# Sheet1.net
KiCad netlist of a schematic drawn in Altium Designer
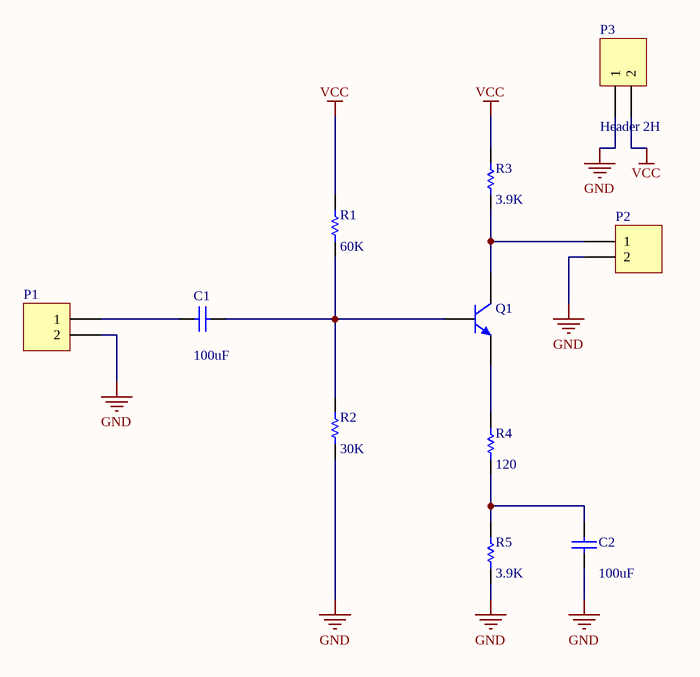
[diagram p0: Sheet1.SchDoc]

(export (version "E")
  (design (tool "Eeschema 10.0.6"))
  (components
    (comp (ref "C1")
      (value "100uF")
      (footprint "RAD-0.3")
      (description "Capacitor")
      (fields (field (name "Comment") "Cap") (field (name "PUBLISHER") "Altium Limited"))
      (libsource (lib "Miscellaneous Devices") (part "Cap"))
    )
    (comp (ref "C2")
      (value "100uF")
      (footprint "RAD-0.3")
      (description "Capacitor")
      (fields (field (name "Comment") "Cap") (field (name "PUBLISHER") "Altium Limited"))
      (libsource (lib "Miscellaneous Devices") (part "Cap"))
    )
    (comp (ref "P1")
      (value "Header 2H")
      (footprint "HDR1X2H")
      (description "Header, 2-Pin, Right Angle")
      (fields (field (name "PUBLISHER") "Altium Limited"))
      (libsource (lib "Miscellaneous Connectors") (part "Header 2H"))
    )
    (comp (ref "P2")
      (value "Header 2H")
      (footprint "HDR1X2H")
      (description "Header, 2-Pin, Right Angle")
      (fields (field (name "PUBLISHER") "Altium Limited"))
      (libsource (lib "") (part "Header 2H_1"))
    )
    (comp (ref "P3")
      (value "Header 2H")
      (footprint "HDR1X2H")
      (description "Header, 2-Pin, Right Angle")
      (fields (field (name "PUBLISHER") "Altium Limited"))
      (libsource (lib "") (part "Header 2H_2"))
    )
    (comp (ref "Q1")
      (value "BC548C")
      (footprint "29-04")
      (description "Amplifier Transistor NPN Silicon")
      (fields (field (name "PUBLISHER") "Altium Limited"))
      (libsource (lib "Motorola Discrete BJT") (part "BC548C"))
    )
    (comp (ref "R1")
      (value "60K")
      (footprint "AXIAL-0.3")
      (description "Resistor")
      (fields (field (name "Comment") "Res1") (field (name "PUBLISHER") "Altium Limited"))
      (libsource (lib "Miscellaneous Devices") (part "Res1"))
    )
    (comp (ref "R2")
      (value "30K")
      (footprint "AXIAL-0.3")
      (description "Resistor")
      (fields (field (name "Comment") "Res1") (field (name "PUBLISHER") "Altium Limited"))
      (libsource (lib "Miscellaneous Devices") (part "Res1"))
    )
    (comp (ref "R3")
      (value "3.9K")
      (footprint "AXIAL-0.3")
      (description "Resistor")
      (fields (field (name "Comment") "Res1") (field (name "PUBLISHER") "Altium Limited"))
      (libsource (lib "Miscellaneous Devices") (part "Res1"))
    )
    (comp (ref "R4")
      (value "120")
      (footprint "AXIAL-0.3")
      (description "Resistor")
      (fields (field (name "Comment") "Res1") (field (name "PUBLISHER") "Altium Limited"))
      (libsource (lib "Miscellaneous Devices") (part "Res1"))
    )
    (comp (ref "R5")
      (value "3.9K")
      (footprint "AXIAL-0.3")
      (description "Resistor")
      (fields (field (name "Comment") "Res1") (field (name "PUBLISHER") "Altium Limited"))
      (libsource (lib "Miscellaneous Devices") (part "Res1"))
    )
  )
  (nets
    (net (code "1") (name "GND") (class "Default")
      (node (ref "C2") (pin "1") (pinfunction "1_1") (pintype "passive"))
      (node (ref "P1") (pin "2") (pinfunction "2_2") (pintype "passive"))
      (node (ref "P2") (pin "2") (pinfunction "2_2") (pintype "passive"))
      (node (ref "P3") (pin "1") (pinfunction "1_1") (pintype "passive"))
      (node (ref "R2") (pin "1") (pinfunction "1_1") (pintype "passive"))
      (node (ref "R5") (pin "1") (pinfunction "1_1") (pintype "passive"))
    )
    (net (code "2") (name "Net-(C1-Pad1)") (class "Default")
      (node (ref "C1") (pin "1") (pinfunction "1_1") (pintype "passive"))
      (node (ref "P1") (pin "1") (pinfunction "1_1") (pintype "passive"))
    )
    (net (code "3") (name "Net-(C2-Pad2)") (class "Default")
      (node (ref "C2") (pin "2") (pinfunction "2_2") (pintype "passive"))
      (node (ref "R4") (pin "1") (pinfunction "1_1") (pintype "passive"))
      (node (ref "R5") (pin "2") (pinfunction "2_2") (pintype "passive"))
    )
    (net (code "4") (name "Net-(Q1-B)") (class "Default")
      (node (ref "C1") (pin "2") (pinfunction "2_2") (pintype "passive"))
      (node (ref "Q1") (pin "2") (pinfunction "B_2") (pintype "passive"))
      (node (ref "R1") (pin "1") (pinfunction "1_1") (pintype "passive"))
      (node (ref "R2") (pin "2") (pinfunction "2_2") (pintype "passive"))
    )
    (net (code "5") (name "Net-(Q1-C)") (class "Default")
      (node (ref "P2") (pin "1") (pinfunction "1_1") (pintype "passive"))
      (node (ref "Q1") (pin "1") (pinfunction "C_1") (pintype "passive"))
      (node (ref "R3") (pin "1") (pinfunction "1_1") (pintype "passive"))
    )
    (net (code "6") (name "Net-(Q1-E)") (class "Default")
      (node (ref "Q1") (pin "3") (pinfunction "E_3") (pintype "passive"))
      (node (ref "R4") (pin "2") (pinfunction "2_2") (pintype "passive"))
    )
    (net (code "7") (name "VCC") (class "Default")
      (node (ref "P3") (pin "2") (pinfunction "2_2") (pintype "passive"))
      (node (ref "R1") (pin "2") (pinfunction "2_2") (pintype "passive"))
      (node (ref "R3") (pin "2") (pinfunction "2_2") (pintype "passive"))
    )
  )
)
